# HMI.net
KiCad netlist of a schematic drawn in Altium Designer
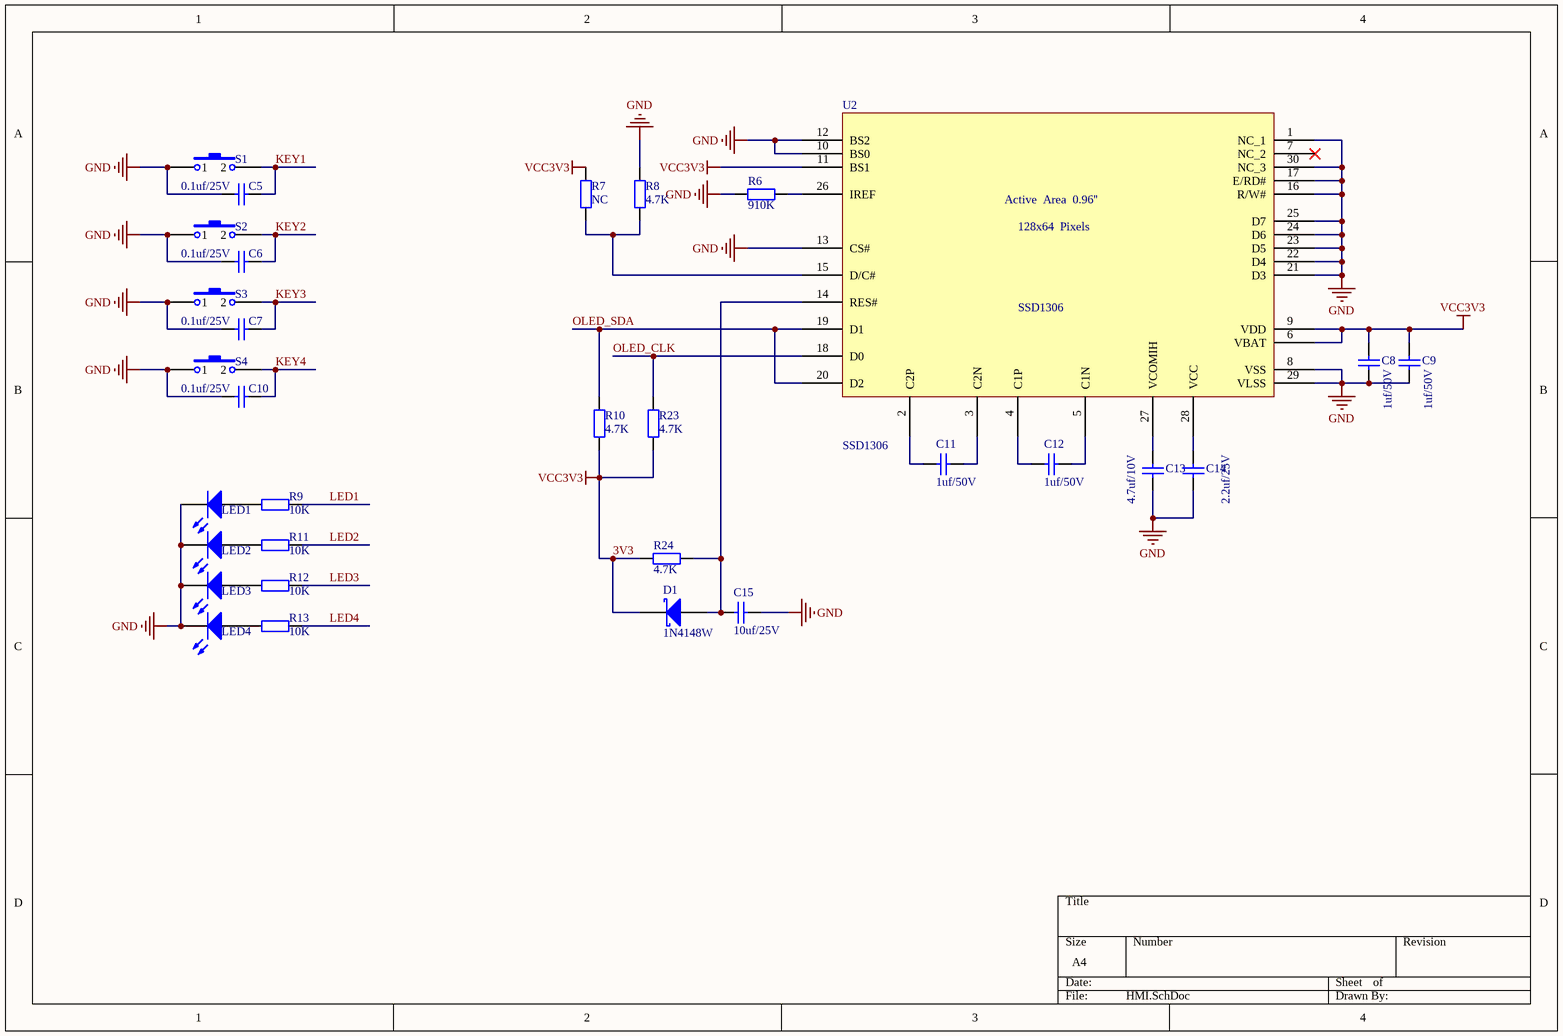
[diagram p0: HMI.SchDoc]

(export (version "E")
  (design (tool "Eeschema 10.0.6"))
  (components
    (comp (ref "C5")
      (value "0.1uf/25V")
      (footprint "R_C_L:C_0603")
      (description "多层片式陶瓷电容器")
      (libsource (lib "R_C_L") (part "C-0603-0.1uf/25V-10%"))
    )
    (comp (ref "C6")
      (value "0.1uf/25V")
      (footprint "R_C_L:C_0603")
      (description "多层片式陶瓷电容器")
      (libsource (lib "R_C_L") (part "C-0603-0.1uf/25V-10%"))
    )
    (comp (ref "C7")
      (value "0.1uf/25V")
      (footprint "R_C_L:C_0603")
      (description "多层片式陶瓷电容器")
      (libsource (lib "R_C_L") (part "C-0603-0.1uf/25V-10%"))
    )
    (comp (ref "C8")
      (value "1uf/50V")
      (footprint "R_C_L:C_0603")
      (description "多层片式陶瓷电容器")
      (libsource (lib "R_C_L") (part "C-0603-1uf/50V-10%"))
    )
    (comp (ref "C9")
      (value "1uf/50V")
      (footprint "R_C_L:C_0603")
      (description "多层片式陶瓷电容器")
      (libsource (lib "R_C_L") (part "C-0603-1uf/50V-10%"))
    )
    (comp (ref "C10")
      (value "0.1uf/25V")
      (footprint "R_C_L:C_0603")
      (description "多层片式陶瓷电容器")
      (libsource (lib "R_C_L") (part "C-0603-0.1uf/25V-10%"))
    )
    (comp (ref "C11")
      (value "1uf/50V")
      (footprint "R_C_L:C_0603")
      (description "多层片式陶瓷电容器")
      (libsource (lib "R_C_L") (part "C-0603-1uf/50V-10%"))
    )
    (comp (ref "C12")
      (value "1uf/50V")
      (footprint "R_C_L:C_0603")
      (description "多层片式陶瓷电容器")
      (libsource (lib "R_C_L") (part "C-0603-1uf/50V-10%"))
    )
    (comp (ref "C13")
      (value "4.7uf/10V")
      (footprint "R_C_L:C_0603")
      (description "多层片式陶瓷电容器")
      (libsource (lib "R_C_L") (part "C-0603-4.7uf/10V-10%"))
    )
    (comp (ref "C14")
      (value "2.2uf/25V")
      (footprint "R_C_L:C_0603")
      (description "多层片式陶瓷电容器")
      (libsource (lib "R_C_L") (part "C-0603-2.2uf/25V-10%"))
    )
    (comp (ref "C15")
      (value "10uf/25V")
      (footprint "R_C_L:C_0603")
      (description "多层片式陶瓷电容器")
      (libsource (lib "R_C_L") (part "C-0603-10uf/25V-20%"))
    )
    (comp (ref "D1")
      (value "1N4148W")
      (footprint "Transistor:SOD123")
      (description "肖特基二极管SOD123")
      (libsource (lib "Transistor") (part "D_Schottky_1N4148W"))
    )
    (comp (ref "LED1")
      (value "19-21SYGC/S530-E2/TR8")
      (footprint "Transistor:LED_0603")
      (description "发光二极管0603黄绿色")
      (libsource (lib "Transistor") (part "LED1_19-21SYGC/S530-E2/TR8"))
    )
    (comp (ref "LED2")
      (value "19-21SYGC/S530-E2/TR8")
      (footprint "Transistor:LED_0603")
      (description "发光二极管0603黄绿色")
      (libsource (lib "Transistor") (part "LED1_19-21SYGC/S530-E2/TR8"))
    )
    (comp (ref "LED3")
      (value "19-21SYGC/S530-E2/TR8")
      (footprint "Transistor:LED_0603")
      (description "发光二极管0603黄绿色")
      (libsource (lib "Transistor") (part "LED1_19-21SYGC/S530-E2/TR8"))
    )
    (comp (ref "LED4")
      (value "19-21SYGC/S530-E2/TR8")
      (footprint "Transistor:LED_0603")
      (description "发光二极管0603黄绿色")
      (libsource (lib "Transistor") (part "LED1_19-21SYGC/S530-E2/TR8"))
    )
    (comp (ref "R6")
      (value "910K")
      (footprint "R_C_L:R_0603")
      (description "通用电阻")
      (libsource (lib "R_C_L") (part "R-0603-698K-1%"))
    )
    (comp (ref "R7")
      (value "NC")
      (footprint "R_C_L:R_0603")
      (description "通用电阻")
      (libsource (lib "R_C_L") (part "R-0603-4.7K-1%"))
    )
    (comp (ref "R8")
      (value "4.7K")
      (footprint "R_C_L:R_0603")
      (description "通用电阻")
      (libsource (lib "R_C_L") (part "R-0603-4.7K-1%"))
    )
    (comp (ref "R9")
      (value "10K")
      (footprint "R_C_L:R_0603")
      (description "通用电阻")
      (libsource (lib "R_C_L") (part "R-0603-10K-1%"))
    )
    (comp (ref "R10")
      (value "4.7K")
      (footprint "R_C_L:R_0603")
      (description "通用电阻")
      (libsource (lib "R_C_L") (part "R-0603-4.7K-1%"))
    )
    (comp (ref "R11")
      (value "10K")
      (footprint "R_C_L:R_0603")
      (description "通用电阻")
      (libsource (lib "R_C_L") (part "R-0603-10K-1%"))
    )
    (comp (ref "R12")
      (value "10K")
      (footprint "R_C_L:R_0603")
      (description "通用电阻")
      (libsource (lib "R_C_L") (part "R-0603-10K-1%"))
    )
    (comp (ref "R13")
      (value "10K")
      (footprint "R_C_L:R_0603")
      (description "通用电阻")
      (libsource (lib "R_C_L") (part "R-0603-10K-1%"))
    )
    (comp (ref "R23")
      (value "4.7K")
      (footprint "R_C_L:R_0603")
      (description "通用电阻")
      (libsource (lib "R_C_L") (part "R-0603-4.7K-1%"))
    )
    (comp (ref "R24")
      (value "4.7K")
      (footprint "R_C_L:R_0603")
      (description "通用电阻")
      (libsource (lib "") (part "R-0603-4.7K-1%_1"))
    )
    (comp (ref "S1")
      (value "K2-1107ST-A4SW-06")
      (footprint "NSP:SW-2P-6*3-SMT")
      (description "轻触开关3.6*6.1*2.5")
      (libsource (lib "NSP") (part "KEY_K2-1107ST-A4SW-06"))
    )
    (comp (ref "S2")
      (value "K2-1107ST-A4SW-06")
      (footprint "NSP:SW-2P-6*3-SMT")
      (description "轻触开关3.6*6.1*2.5")
      (libsource (lib "NSP") (part "KEY_K2-1107ST-A4SW-06"))
    )
    (comp (ref "S3")
      (value "K2-1107ST-A4SW-06")
      (footprint "NSP:SW-2P-6*3-SMT")
      (description "轻触开关3.6*6.1*2.5")
      (libsource (lib "NSP") (part "KEY_K2-1107ST-A4SW-06"))
    )
    (comp (ref "S4")
      (value "K2-1107ST-A4SW-06")
      (footprint "NSP:SW-2P-6*3-SMT")
      (description "轻触开关3.6*6.1*2.5")
      (libsource (lib "NSP") (part "KEY_K2-1107ST-A4SW-06"))
    )
    (comp (ref "U2")
      (value "SSD1306")
      (footprint "Analog:显示屏1.3\"")
      (description "OLED显示模块主控芯片")
      (libsource (lib "Analog") (part "SSD1306"))
    )
  )
  (nets
    (net (code "1") (name "/KEY1") (class "Default")
      (node (ref "C5") (pin "2") (pinfunction "2_2") (pintype "passive"))
      (node (ref "S1") (pin "2") (pinfunction "2_2") (pintype "passive"))
    )
    (net (code "2") (name "/KEY2") (class "Default")
      (node (ref "C6") (pin "2") (pinfunction "2_2") (pintype "passive"))
      (node (ref "S2") (pin "2") (pinfunction "2_2") (pintype "passive"))
    )
    (net (code "3") (name "/KEY3") (class "Default")
      (node (ref "C7") (pin "2") (pinfunction "2_2") (pintype "passive"))
      (node (ref "S3") (pin "2") (pinfunction "2_2") (pintype "passive"))
    )
    (net (code "4") (name "/KEY4") (class "Default")
      (node (ref "C10") (pin "2") (pinfunction "2_2") (pintype "passive"))
      (node (ref "S4") (pin "2") (pinfunction "2_2") (pintype "passive"))
    )
    (net (code "5") (name "/LED1") (class "Default")
      (node (ref "R9") (pin "2") (pinfunction "2_2") (pintype "passive"))
    )
    (net (code "6") (name "/LED2") (class "Default")
      (node (ref "R11") (pin "2") (pinfunction "2_2") (pintype "passive"))
    )
    (net (code "7") (name "/LED3") (class "Default")
      (node (ref "R12") (pin "2") (pinfunction "2_2") (pintype "passive"))
    )
    (net (code "8") (name "/LED4") (class "Default")
      (node (ref "R13") (pin "2") (pinfunction "2_2") (pintype "passive"))
    )
    (net (code "9") (name "/OLED_CLK") (class "Default")
      (node (ref "R23") (pin "2") (pinfunction "2_2") (pintype "passive"))
      (node (ref "U2") (pin "18") (pinfunction "D0_18") (pintype "passive"))
    )
    (net (code "10") (name "/OLED_SDA") (class "Default")
      (node (ref "R10") (pin "2") (pinfunction "2_2") (pintype "passive"))
      (node (ref "U2") (pin "19") (pinfunction "D1_19") (pintype "passive"))
      (node (ref "U2") (pin "20") (pinfunction "D2_20") (pintype "passive"))
    )
    (net (code "11") (name "GND") (class "Default")
      (node (ref "C10") (pin "1") (pinfunction "1_1") (pintype "passive"))
      (node (ref "C13") (pin "1") (pinfunction "1_1") (pintype "passive"))
      (node (ref "C14") (pin "1") (pinfunction "1_1") (pintype "passive"))
      (node (ref "C15") (pin "2") (pinfunction "2_2") (pintype "passive"))
      (node (ref "C5") (pin "1") (pinfunction "1_1") (pintype "passive"))
      (node (ref "C6") (pin "1") (pinfunction "1_1") (pintype "passive"))
      (node (ref "C7") (pin "1") (pinfunction "1_1") (pintype "passive"))
      (node (ref "C8") (pin "1") (pinfunction "1_1") (pintype "passive"))
      (node (ref "C9") (pin "1") (pinfunction "1_1") (pintype "passive"))
      (node (ref "LED1") (pin "2") (pinfunction "Cathode_2") (pintype "passive"))
      (node (ref "LED2") (pin "2") (pinfunction "Cathode_2") (pintype "passive"))
      (node (ref "LED3") (pin "2") (pinfunction "Cathode_2") (pintype "passive"))
      (node (ref "LED4") (pin "2") (pinfunction "Cathode_2") (pintype "passive"))
      (node (ref "R6") (pin "1") (pinfunction "1_1") (pintype "passive"))
      (node (ref "R8") (pin "2") (pinfunction "2_2") (pintype "passive"))
      (node (ref "S1") (pin "1") (pinfunction "1_1") (pintype "passive"))
      (node (ref "S2") (pin "1") (pinfunction "1_1") (pintype "passive"))
      (node (ref "S3") (pin "1") (pinfunction "1_1") (pintype "passive"))
      (node (ref "S4") (pin "1") (pinfunction "1_1") (pintype "passive"))
      (node (ref "U2") (pin "1") (pinfunction "NC_1_1") (pintype "passive"))
      (node (ref "U2") (pin "10") (pinfunction "BS0_10") (pintype "passive"))
      (node (ref "U2") (pin "12") (pinfunction "BS2_12") (pintype "passive"))
      (node (ref "U2") (pin "13") (pinfunction "CS#_13") (pintype "passive"))
      (node (ref "U2") (pin "16") (pinfunction "R/W#_16") (pintype "passive"))
      (node (ref "U2") (pin "17") (pinfunction "E/RD#_17") (pintype "passive"))
      (node (ref "U2") (pin "21") (pinfunction "D3_21") (pintype "passive"))
      (node (ref "U2") (pin "22") (pinfunction "D4_22") (pintype "passive"))
      (node (ref "U2") (pin "23") (pinfunction "D5_23") (pintype "passive"))
      (node (ref "U2") (pin "24") (pinfunction "D6_24") (pintype "passive"))
      (node (ref "U2") (pin "25") (pinfunction "D7_25") (pintype "passive"))
      (node (ref "U2") (pin "29") (pinfunction "VLSS_29") (pintype "passive"))
      (node (ref "U2") (pin "30") (pinfunction "NC_3_30") (pintype "passive"))
      (node (ref "U2") (pin "8") (pinfunction "VSS_8") (pintype "passive"))
    )
    (net (code "12") (name "Net-(D1-A)") (class "Default")
      (node (ref "C15") (pin "1") (pinfunction "1_1") (pintype "passive"))
      (node (ref "D1") (pin "1") (pinfunction "A_1") (pintype "passive"))
      (node (ref "R24") (pin "1") (pinfunction "1_1") (pintype "passive"))
      (node (ref "U2") (pin "14") (pinfunction "RES#_14") (pintype "passive"))
    )
    (net (code "13") (name "Net-(LED1-Anode)") (class "Default")
      (node (ref "LED1") (pin "1") (pinfunction "Anode_1") (pintype "passive"))
      (node (ref "R9") (pin "1") (pinfunction "1_1") (pintype "passive"))
    )
    (net (code "14") (name "Net-(LED2-Anode)") (class "Default")
      (node (ref "LED2") (pin "1") (pinfunction "Anode_1") (pintype "passive"))
      (node (ref "R11") (pin "1") (pinfunction "1_1") (pintype "passive"))
    )
    (net (code "15") (name "Net-(LED3-Anode)") (class "Default")
      (node (ref "LED3") (pin "1") (pinfunction "Anode_1") (pintype "passive"))
      (node (ref "R12") (pin "1") (pinfunction "1_1") (pintype "passive"))
    )
    (net (code "16") (name "Net-(LED4-Anode)") (class "Default")
      (node (ref "LED4") (pin "1") (pinfunction "Anode_1") (pintype "passive"))
      (node (ref "R13") (pin "1") (pinfunction "1_1") (pintype "passive"))
    )
    (net (code "17") (name "Net-(U2-C1N)") (class "Default")
      (node (ref "C12") (pin "2") (pinfunction "2_2") (pintype "passive"))
      (node (ref "U2") (pin "5") (pinfunction "C1N_5") (pintype "passive"))
    )
    (net (code "18") (name "Net-(U2-C1P)") (class "Default")
      (node (ref "C12") (pin "1") (pinfunction "1_1") (pintype "passive"))
      (node (ref "U2") (pin "4") (pinfunction "C1P_4") (pintype "passive"))
    )
    (net (code "19") (name "Net-(U2-C2N)") (class "Default")
      (node (ref "C11") (pin "2") (pinfunction "2_2") (pintype "passive"))
      (node (ref "U2") (pin "3") (pinfunction "C2N_3") (pintype "passive"))
    )
    (net (code "20") (name "Net-(U2-C2P)") (class "Default")
      (node (ref "C11") (pin "1") (pinfunction "1_1") (pintype "passive"))
      (node (ref "U2") (pin "2") (pinfunction "C2P_2") (pintype "passive"))
    )
    (net (code "21") (name "Net-(U2-D{slash}C#)") (class "Default")
      (node (ref "R7") (pin "1") (pinfunction "1_1") (pintype "passive"))
      (node (ref "R8") (pin "1") (pinfunction "1_1") (pintype "passive"))
      (node (ref "U2") (pin "15") (pinfunction "D/C#_15") (pintype "passive"))
    )
    (net (code "22") (name "Net-(U2-IREF)") (class "Default")
      (node (ref "R6") (pin "2") (pinfunction "2_2") (pintype "passive"))
      (node (ref "U2") (pin "26") (pinfunction "IREF_26") (pintype "passive"))
    )
    (net (code "23") (name "Net-(U2-VCC)") (class "Default")
      (node (ref "C14") (pin "2") (pinfunction "2_2") (pintype "passive"))
      (node (ref "U2") (pin "28") (pinfunction "VCC_28") (pintype "passive"))
    )
    (net (code "24") (name "Net-(U2-VCOMIH)") (class "Default")
      (node (ref "C13") (pin "2") (pinfunction "2_2") (pintype "passive"))
      (node (ref "U2") (pin "27") (pinfunction "VCOMIH_27") (pintype "passive"))
    )
    (net (code "25") (name "VCC3V3") (class "Default")
      (node (ref "C8") (pin "2") (pinfunction "2_2") (pintype "passive"))
      (node (ref "C9") (pin "2") (pinfunction "2_2") (pintype "passive"))
      (node (ref "D1") (pin "2") (pinfunction "K_2") (pintype "passive"))
      (node (ref "R10") (pin "1") (pinfunction "1_1") (pintype "passive"))
      (node (ref "R23") (pin "1") (pinfunction "1_1") (pintype "passive"))
      (node (ref "R24") (pin "2") (pinfunction "2_2") (pintype "passive"))
      (node (ref "R7") (pin "2") (pinfunction "2_2") (pintype "passive"))
      (node (ref "U2") (pin "11") (pinfunction "BS1_11") (pintype "passive"))
      (node (ref "U2") (pin "6") (pinfunction "VBAT_6") (pintype "passive"))
      (node (ref "U2") (pin "9") (pinfunction "VDD_9") (pintype "passive"))
    )
    (net (code "26") (name "unconnected-(U2-NC_2-Pad7)") (class "Default")
      (node (ref "U2") (pin "7") (pinfunction "NC_2_7") (pintype "passive+no_connect"))
    )
  )
)
